# LAN8870_PINOUT.net
KiCad netlist of a schematic drawn in Altium Designer
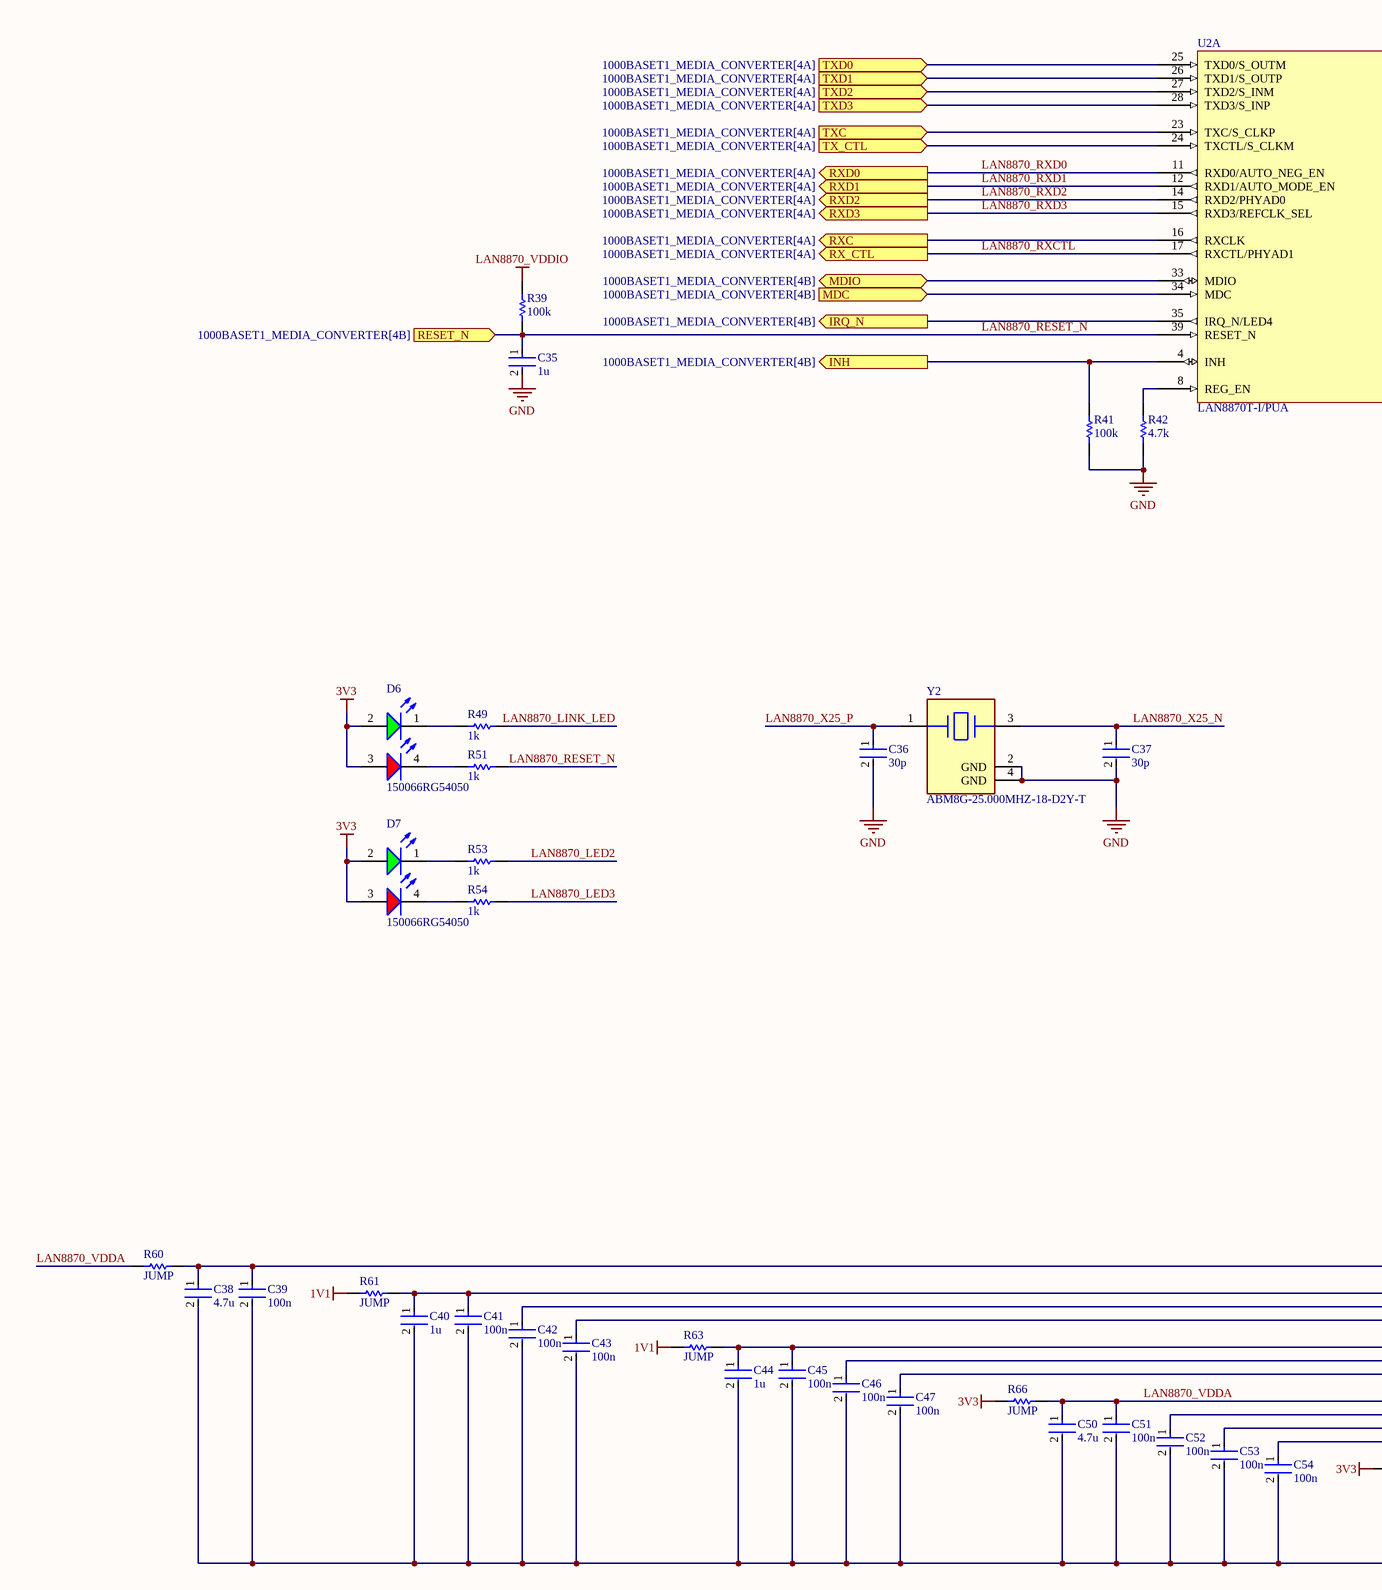
[diagram p0: LAN8870_PINOUT.SchDoc, left]
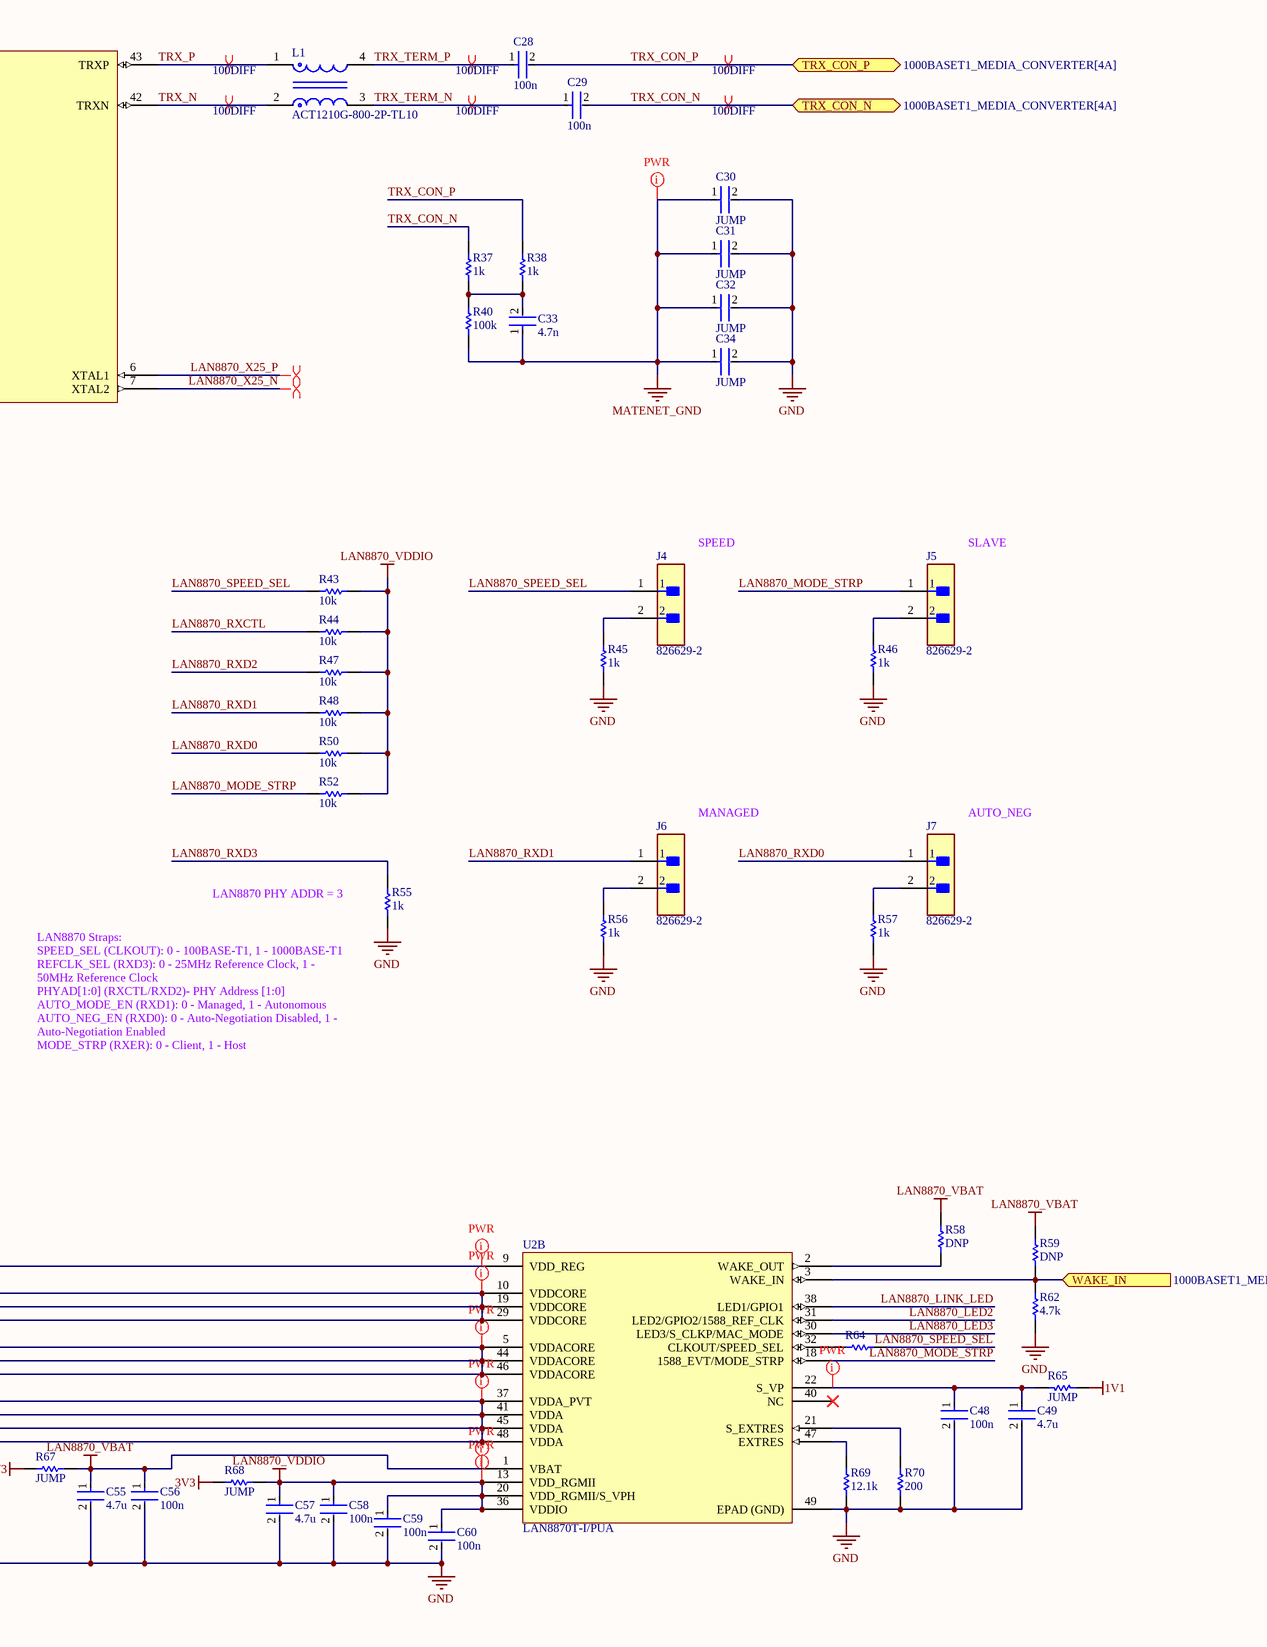
[diagram p1: LAN8870_PINOUT.SchDoc, right]

(export (version "E")
  (design (tool "Eeschema 10.0.6"))
  (components
    (comp (ref "C28")
      (value "100n")
      (footprint "FP-0402-L_1_0_0_05-W_0_5-IPC_A")
      (description "LARGE PADS, 0402 CAP, CHANGE COMMENT TO MATCH REAL P/N")
      (libsource (lib "Space Concordia") (part "b4654b650e69147ec39a6b967a45e02"))
    )
    (comp (ref "C29")
      (value "100n")
      (footprint "FP-0402-L_1_0_0_05-W_0_5-IPC_A")
      (description "LARGE PADS, 0402 CAP, CHANGE COMMENT TO MATCH REAL P/N")
      (libsource (lib "Space Concordia") (part "b4654b650e69147ec39a6b967a45e02"))
    )
    (comp (ref "C30")
      (value "JUMP")
      (footprint "FP-0402-L_1_0_0_05-W_0_5-IPC_A")
      (description "LARGE PADS, 0402 CAP, CHANGE COMMENT TO MATCH REAL P/N")
      (libsource (lib "Space Concordia") (part "b4654b650e69147ec39a6b967a45e02"))
    )
    (comp (ref "C31")
      (value "JUMP")
      (footprint "FP-0402-L_1_0_0_05-W_0_5-IPC_A")
      (description "LARGE PADS, 0402 CAP, CHANGE COMMENT TO MATCH REAL P/N")
      (libsource (lib "Space Concordia") (part "b4654b650e69147ec39a6b967a45e02"))
    )
    (comp (ref "C32")
      (value "JUMP")
      (footprint "FP-0402-L_1_0_0_05-W_0_5-IPC_A")
      (description "LARGE PADS, 0402 CAP, CHANGE COMMENT TO MATCH REAL P/N")
      (libsource (lib "Space Concordia") (part "b4654b650e69147ec39a6b967a45e02"))
    )
    (comp (ref "C33")
      (value "4.7n")
      (footprint "FP-0402-L_1_0_0_05-W_0_5-IPC_A")
      (description "LARGE PADS, 0402 CAP, CHANGE COMMENT TO MATCH REAL P/N")
      (libsource (lib "Space Concordia") (part "b4654b650e69147ec39a6b967a45e02"))
    )
    (comp (ref "C34")
      (value "JUMP")
      (footprint "FP-0402-L_1_0_0_05-W_0_5-IPC_A")
      (description "LARGE PADS, 0402 CAP, CHANGE COMMENT TO MATCH REAL P/N")
      (libsource (lib "Space Concordia") (part "b4654b650e69147ec39a6b967a45e02"))
    )
    (comp (ref "C35")
      (value "1u")
      (footprint "FP-0402-L_1_0_0_05-W_0_5-IPC_A")
      (description "LARGE PADS, 0402 CAP, CHANGE COMMENT TO MATCH REAL P/N")
      (libsource (lib "Space Concordia") (part "b4654b650e69147ec39a6b967a45e02"))
    )
    (comp (ref "C36")
      (value "30p")
      (footprint "FP-0402-L_1_0_0_05-W_0_5-IPC_A")
      (description "LARGE PADS, 0402 CAP, CHANGE COMMENT TO MATCH REAL P/N")
      (libsource (lib "Space Concordia") (part "b4654b650e69147ec39a6b967a45e02"))
    )
    (comp (ref "C37")
      (value "30p")
      (footprint "FP-0402-L_1_0_0_05-W_0_5-IPC_A")
      (description "LARGE PADS, 0402 CAP, CHANGE COMMENT TO MATCH REAL P/N")
      (libsource (lib "Space Concordia") (part "b4654b650e69147ec39a6b967a45e02"))
    )
    (comp (ref "C38")
      (value "4.7u")
      (footprint "FP-0402-L_1_0_0_05-W_0_5-IPC_A")
      (description "LARGE PADS, 0402 CAP, CHANGE COMMENT TO MATCH REAL P/N")
      (libsource (lib "Space Concordia") (part "b4654b650e69147ec39a6b967a45e02"))
    )
    (comp (ref "C39")
      (value "100n")
      (footprint "FP-0402-L_1_0_0_05-W_0_5-IPC_A")
      (description "LARGE PADS, 0402 CAP, CHANGE COMMENT TO MATCH REAL P/N")
      (libsource (lib "Space Concordia") (part "b4654b650e69147ec39a6b967a45e02"))
    )
    (comp (ref "C40")
      (value "1u")
      (footprint "FP-0402-L_1_0_0_05-W_0_5-IPC_A")
      (description "LARGE PADS, 0402 CAP, CHANGE COMMENT TO MATCH REAL P/N")
      (libsource (lib "Space Concordia") (part "b4654b650e69147ec39a6b967a45e02"))
    )
    (comp (ref "C41")
      (value "100n")
      (footprint "FP-0402-L_1_0_0_05-W_0_5-IPC_A")
      (description "LARGE PADS, 0402 CAP, CHANGE COMMENT TO MATCH REAL P/N")
      (libsource (lib "Space Concordia") (part "b4654b650e69147ec39a6b967a45e02"))
    )
    (comp (ref "C42")
      (value "100n")
      (footprint "FP-0402-L_1_0_0_05-W_0_5-IPC_A")
      (description "LARGE PADS, 0402 CAP, CHANGE COMMENT TO MATCH REAL P/N")
      (libsource (lib "Space Concordia") (part "b4654b650e69147ec39a6b967a45e02"))
    )
    (comp (ref "C43")
      (value "100n")
      (footprint "FP-0402-L_1_0_0_05-W_0_5-IPC_A")
      (description "LARGE PADS, 0402 CAP, CHANGE COMMENT TO MATCH REAL P/N")
      (libsource (lib "Space Concordia") (part "b4654b650e69147ec39a6b967a45e02"))
    )
    (comp (ref "C44")
      (value "1u")
      (footprint "FP-0402-L_1_0_0_05-W_0_5-IPC_A")
      (description "LARGE PADS, 0402 CAP, CHANGE COMMENT TO MATCH REAL P/N")
      (libsource (lib "Space Concordia") (part "b4654b650e69147ec39a6b967a45e02"))
    )
    (comp (ref "C45")
      (value "100n")
      (footprint "FP-0402-L_1_0_0_05-W_0_5-IPC_A")
      (description "LARGE PADS, 0402 CAP, CHANGE COMMENT TO MATCH REAL P/N")
      (libsource (lib "Space Concordia") (part "b4654b650e69147ec39a6b967a45e02"))
    )
    (comp (ref "C46")
      (value "100n")
      (footprint "FP-0402-L_1_0_0_05-W_0_5-IPC_A")
      (description "LARGE PADS, 0402 CAP, CHANGE COMMENT TO MATCH REAL P/N")
      (libsource (lib "Space Concordia") (part "b4654b650e69147ec39a6b967a45e02"))
    )
    (comp (ref "C47")
      (value "100n")
      (footprint "FP-0402-L_1_0_0_05-W_0_5-IPC_A")
      (description "LARGE PADS, 0402 CAP, CHANGE COMMENT TO MATCH REAL P/N")
      (libsource (lib "Space Concordia") (part "b4654b650e69147ec39a6b967a45e02"))
    )
    (comp (ref "C48")
      (value "100n")
      (footprint "FP-0402-L_1_0_0_05-W_0_5-IPC_A")
      (description "LARGE PADS, 0402 CAP, CHANGE COMMENT TO MATCH REAL P/N")
      (libsource (lib "Space Concordia") (part "b4654b650e69147ec39a6b967a45e02"))
    )
    (comp (ref "C49")
      (value "4.7u")
      (footprint "FP-0402-L_1_0_0_05-W_0_5-IPC_A")
      (description "LARGE PADS, 0402 CAP, CHANGE COMMENT TO MATCH REAL P/N")
      (libsource (lib "Space Concordia") (part "b4654b650e69147ec39a6b967a45e02"))
    )
    (comp (ref "C50")
      (value "4.7u")
      (footprint "FP-0402-L_1_0_0_05-W_0_5-IPC_A")
      (description "LARGE PADS, 0402 CAP, CHANGE COMMENT TO MATCH REAL P/N")
      (libsource (lib "Space Concordia") (part "b4654b650e69147ec39a6b967a45e02"))
    )
    (comp (ref "C51")
      (value "100n")
      (footprint "FP-0402-L_1_0_0_05-W_0_5-IPC_A")
      (description "LARGE PADS, 0402 CAP, CHANGE COMMENT TO MATCH REAL P/N")
      (libsource (lib "Space Concordia") (part "b4654b650e69147ec39a6b967a45e02"))
    )
    (comp (ref "C52")
      (value "100n")
      (footprint "FP-0402-L_1_0_0_05-W_0_5-IPC_A")
      (description "LARGE PADS, 0402 CAP, CHANGE COMMENT TO MATCH REAL P/N")
      (libsource (lib "Space Concordia") (part "b4654b650e69147ec39a6b967a45e02"))
    )
    (comp (ref "C53")
      (value "100n")
      (footprint "FP-0402-L_1_0_0_05-W_0_5-IPC_A")
      (description "LARGE PADS, 0402 CAP, CHANGE COMMENT TO MATCH REAL P/N")
      (libsource (lib "Space Concordia") (part "b4654b650e69147ec39a6b967a45e02"))
    )
    (comp (ref "C54")
      (value "100n")
      (footprint "FP-0402-L_1_0_0_05-W_0_5-IPC_A")
      (description "LARGE PADS, 0402 CAP, CHANGE COMMENT TO MATCH REAL P/N")
      (libsource (lib "Space Concordia") (part "b4654b650e69147ec39a6b967a45e02"))
    )
    (comp (ref "C55")
      (value "4.7u")
      (footprint "FP-0402-L_1_0_0_05-W_0_5-IPC_A")
      (description "LARGE PADS, 0402 CAP, CHANGE COMMENT TO MATCH REAL P/N")
      (libsource (lib "Space Concordia") (part "b4654b650e69147ec39a6b967a45e02"))
    )
    (comp (ref "C56")
      (value "100n")
      (footprint "FP-0402-L_1_0_0_05-W_0_5-IPC_A")
      (description "LARGE PADS, 0402 CAP, CHANGE COMMENT TO MATCH REAL P/N")
      (libsource (lib "Space Concordia") (part "b4654b650e69147ec39a6b967a45e02"))
    )
    (comp (ref "C57")
      (value "4.7u")
      (footprint "FP-0402-L_1_0_0_05-W_0_5-IPC_A")
      (description "LARGE PADS, 0402 CAP, CHANGE COMMENT TO MATCH REAL P/N")
      (libsource (lib "Space Concordia") (part "b4654b650e69147ec39a6b967a45e02"))
    )
    (comp (ref "C58")
      (value "100n")
      (footprint "FP-0402-L_1_0_0_05-W_0_5-IPC_A")
      (description "LARGE PADS, 0402 CAP, CHANGE COMMENT TO MATCH REAL P/N")
      (libsource (lib "Space Concordia") (part "b4654b650e69147ec39a6b967a45e02"))
    )
    (comp (ref "C59")
      (value "100n")
      (footprint "FP-0402-L_1_0_0_05-W_0_5-IPC_A")
      (description "LARGE PADS, 0402 CAP, CHANGE COMMENT TO MATCH REAL P/N")
      (libsource (lib "Space Concordia") (part "b4654b650e69147ec39a6b967a45e02"))
    )
    (comp (ref "C60")
      (value "100n")
      (footprint "FP-0402-L_1_0_0_05-W_0_5-IPC_A")
      (description "LARGE PADS, 0402 CAP, CHANGE COMMENT TO MATCH REAL P/N")
      (libsource (lib "Space Concordia") (part "b4654b650e69147ec39a6b967a45e02"))
    )
    (comp (ref "D6")
      (value "150066RG54050")
      (footprint "WL-SBCD_0606")
      (description "Led, Red/Grn, 180Mcd/230Mcd, 624Nm/525Nm Rohs Compliant: Yes")
      (fields (field (name "SOURCE") "rgled.SchLib"))
      (libsource (lib "Space Concordia") (part "CMP-004-00034-2"))
    )
    (comp (ref "D7")
      (value "150066RG54050")
      (footprint "WL-SBCD_0606")
      (description "Led, Red/Grn, 180Mcd/230Mcd, 624Nm/525Nm Rohs Compliant: Yes")
      (fields (field (name "SOURCE") "rgled.SchLib"))
      (libsource (lib "Space Concordia") (part "CMP-004-00034-2"))
    )
    (comp (ref "J4")
      (value "826629-2")
      (footprint "FP-826629-2-MFG")
      (description "CONN HEADER VERT 2POS 2.54MM")
      (libsource (lib "Altium Content Vault") (part "3bc925449376181038e59eaffc5286c"))
    )
    (comp (ref "J5")
      (value "826629-2")
      (footprint "FP-826629-2-MFG")
      (description "CONN HEADER VERT 2POS 2.54MM")
      (libsource (lib "Altium Content Vault") (part "3bc925449376181038e59eaffc5286c"))
    )
    (comp (ref "J6")
      (value "826629-2")
      (footprint "FP-826629-2-MFG")
      (description "CONN HEADER VERT 2POS 2.54MM")
      (libsource (lib "Altium Content Vault") (part "3bc925449376181038e59eaffc5286c"))
    )
    (comp (ref "J7")
      (value "826629-2")
      (footprint "FP-826629-2-MFG")
      (description "CONN HEADER VERT 2POS 2.54MM")
      (libsource (lib "Altium Content Vault") (part "3bc925449376181038e59eaffc5286c"))
    )
    (comp (ref "L1")
      (value "ACT1210G-800-2P-TL10")
      (footprint "FP-ACT1210G-800-2P-TL10-MFG")
      (description "CMC 80UH 70MA 2LN 3.8KOHM SMD")
      (libsource (lib "Altium Content Vault") (part "b4b74a627ea9af473eaab86227aab92"))
    )
    (comp (ref "R37")
      (value "1k")
      (footprint "R0603B")
      (description "Resistor")
      (libsource (lib "Space Concordia") (part "Resistor"))
    )
    (comp (ref "R38")
      (value "1k")
      (footprint "R0603B")
      (description "Resistor")
      (libsource (lib "Space Concordia") (part "Resistor"))
    )
    (comp (ref "R39")
      (value "100k")
      (footprint "R0603B")
      (description "Resistor")
      (libsource (lib "Space Concordia") (part "Resistor"))
    )
    (comp (ref "R40")
      (value "100k")
      (footprint "R0603B")
      (description "Resistor")
      (libsource (lib "Space Concordia") (part "Resistor"))
    )
    (comp (ref "R41")
      (value "100k")
      (footprint "R0603B")
      (description "Resistor")
      (libsource (lib "Space Concordia") (part "Resistor"))
    )
    (comp (ref "R42")
      (value "4.7k")
      (footprint "R0603B")
      (description "Resistor")
      (libsource (lib "Space Concordia") (part "Resistor"))
    )
    (comp (ref "R43")
      (value "10k")
      (footprint "R0603B")
      (description "Resistor")
      (libsource (lib "Space Concordia") (part "Resistor"))
    )
    (comp (ref "R44")
      (value "10k")
      (footprint "R0603B")
      (description "Resistor")
      (libsource (lib "Space Concordia") (part "Resistor"))
    )
    (comp (ref "R45")
      (value "1k")
      (footprint "R0603B")
      (description "Resistor")
      (libsource (lib "Space Concordia") (part "Resistor"))
    )
    (comp (ref "R46")
      (value "1k")
      (footprint "R0603B")
      (description "Resistor")
      (libsource (lib "Space Concordia") (part "Resistor"))
    )
    (comp (ref "R47")
      (value "10k")
      (footprint "R0603B")
      (description "Resistor")
      (libsource (lib "Space Concordia") (part "Resistor"))
    )
    (comp (ref "R48")
      (value "10k")
      (footprint "R0603B")
      (description "Resistor")
      (libsource (lib "Space Concordia") (part "Resistor"))
    )
    (comp (ref "R49")
      (value "1k")
      (footprint "R0603B")
      (description "Resistor")
      (libsource (lib "Space Concordia") (part "Resistor"))
    )
    (comp (ref "R50")
      (value "10k")
      (footprint "R0603B")
      (description "Resistor")
      (libsource (lib "Space Concordia") (part "Resistor"))
    )
    (comp (ref "R51")
      (value "1k")
      (footprint "R0603B")
      (description "Resistor")
      (libsource (lib "Space Concordia") (part "Resistor"))
    )
    (comp (ref "R52")
      (value "10k")
      (footprint "R0603B")
      (description "Resistor")
      (libsource (lib "Space Concordia") (part "Resistor"))
    )
    (comp (ref "R53")
      (value "1k")
      (footprint "R0603B")
      (description "Resistor")
      (libsource (lib "Space Concordia") (part "Resistor"))
    )
    (comp (ref "R54")
      (value "1k")
      (footprint "R0603B")
      (description "Resistor")
      (libsource (lib "Space Concordia") (part "Resistor"))
    )
    (comp (ref "R55")
      (value "1k")
      (footprint "R0603B")
      (description "Resistor")
      (libsource (lib "Space Concordia") (part "Resistor"))
    )
    (comp (ref "R56")
      (value "1k")
      (footprint "R0603B")
      (description "Resistor")
      (libsource (lib "Space Concordia") (part "Resistor"))
    )
    (comp (ref "R57")
      (value "1k")
      (footprint "R0603B")
      (description "Resistor")
      (libsource (lib "Space Concordia") (part "Resistor"))
    )
    (comp (ref "R58")
      (value "DNP")
      (footprint "R0603B")
      (description "Resistor")
      (libsource (lib "Space Concordia") (part "Resistor"))
    )
    (comp (ref "R59")
      (value "DNP")
      (footprint "R0603B")
      (description "Resistor")
      (libsource (lib "Space Concordia") (part "Resistor"))
    )
    (comp (ref "R60")
      (value "JUMP")
      (footprint "R0603B")
      (description "Resistor")
      (libsource (lib "Space Concordia") (part "Resistor"))
    )
    (comp (ref "R61")
      (value "JUMP")
      (footprint "R0603B")
      (description "Resistor")
      (libsource (lib "Space Concordia") (part "Resistor"))
    )
    (comp (ref "R62")
      (value "4.7k")
      (footprint "R0603B")
      (description "Resistor")
      (libsource (lib "Space Concordia") (part "Resistor"))
    )
    (comp (ref "R63")
      (value "JUMP")
      (footprint "R0603B")
      (description "Resistor")
      (libsource (lib "Space Concordia") (part "Resistor"))
    )
    (comp (ref "R64")
      (value "0402 JUMPER")
      (footprint "RESC1005X40X25ML05T05")
      (description "READ THE NAME")
      (libsource (lib "Space Concordia") (part "CMP-009-00206-2"))
    )
    (comp (ref "R65")
      (value "JUMP")
      (footprint "R0603B")
      (description "Resistor")
      (libsource (lib "Space Concordia") (part "Resistor"))
    )
    (comp (ref "R66")
      (value "JUMP")
      (footprint "R0603B")
      (description "Resistor")
      (libsource (lib "Space Concordia") (part "Resistor"))
    )
    (comp (ref "R67")
      (value "JUMP")
      (footprint "R0603B")
      (description "Resistor")
      (libsource (lib "Space Concordia") (part "Resistor"))
    )
    (comp (ref "R68")
      (value "JUMP")
      (footprint "R0603B")
      (description "Resistor")
      (libsource (lib "Space Concordia") (part "Resistor"))
    )
    (comp (ref "R69")
      (value "12.1k")
      (footprint "R0603B")
      (description "Resistor")
      (libsource (lib "Space Concordia") (part "Resistor"))
    )
    (comp (ref "R70")
      (value "200")
      (footprint "R0603B")
      (description "Resistor")
      (libsource (lib "Space Concordia") (part "Resistor"))
    )
    (comp (ref "U2")
      (value "LAN8870T-I/PUA")
      (footprint "QFN50P700X700X100_HS-49N")
      (description "100/1000BASE-T1 Rgmii/sgmii Phy")
      (libsource (lib "Space Concordia") (part "LAN8870T-I_PUA"))
    )
    (comp (ref "Y2")
      (value "ABM8G-25.000MHZ-18-D2Y-T")
      (footprint "FP-ABM8G-MFG")
      (description "Crystal 25MHz ±20ppm (Tol) ±30ppm (Stability) 18pF FUND 60Ω 4-Pin SMD T/R")
      (fields (field (name "TOLERANCE") "20ppm"))
      (libsource (lib "Altium Content Vault") (part "48e526d86b7f2615d98721063c72f49"))
    )
  )
  (nets
    (net (code "1") (name "/INH") (class "Default")
      (node (ref "R41") (pin "1") (pinfunction "1_1") (pintype "passive"))
      (node (ref "U2") (pin "4") (pinfunction "INH_4") (pintype "bidirectional"))
    )
    (net (code "2") (name "/IRQ_N") (class "Default")
      (node (ref "U2") (pin "35") (pinfunction "IRQ_N/LED4_35") (pintype "output"))
    )
    (net (code "3") (name "/LAN8870_LED2") (class "Default")
      (node (ref "R53") (pin "2") (pinfunction "2_2") (pintype "passive"))
      (node (ref "U2") (pin "31") (pinfunction "LED2/GPIO2/1588_REF_CLK_31") (pintype "bidirectional"))
    )
    (net (code "4") (name "/LAN8870_LED3") (class "Default")
      (node (ref "R54") (pin "2") (pinfunction "2_2") (pintype "passive"))
      (node (ref "U2") (pin "30") (pinfunction "LED3/S_CLKP/MAC_MODE_30") (pintype "bidirectional"))
    )
    (net (code "5") (name "/LAN8870_LINK_LED") (class "Default")
      (node (ref "R49") (pin "2") (pinfunction "2_2") (pintype "passive"))
      (node (ref "U2") (pin "38") (pinfunction "LED1/GPIO1_38") (pintype "bidirectional"))
    )
    (net (code "6") (name "/LAN8870_MODE_STRP") (class "Default")
      (node (ref "J5") (pin "1") (pinfunction "1_1") (pintype "passive"))
      (node (ref "R52") (pin "1") (pinfunction "1_1") (pintype "passive"))
      (node (ref "U2") (pin "18") (pinfunction "1588_EVT/MODE_STRP_18") (pintype "bidirectional"))
    )
    (net (code "7") (name "/LAN8870_RESET_N") (class "Default")
      (node (ref "C35") (pin "1") (pinfunction "1_1") (pintype "passive"))
      (node (ref "R39") (pin "2") (pinfunction "2_2") (pintype "passive"))
      (node (ref "R51") (pin "2") (pinfunction "2_2") (pintype "passive"))
      (node (ref "U2") (pin "39") (pinfunction "RESET_N_39") (pintype "input"))
    )
    (net (code "8") (name "/LAN8870_RXCTL") (class "Default")
      (node (ref "R44") (pin "2") (pinfunction "2_2") (pintype "passive"))
      (node (ref "U2") (pin "17") (pinfunction "RXCTL/PHYAD1_17") (pintype "output"))
    )
    (net (code "9") (name "/LAN8870_RXD0") (class "Default")
      (node (ref "J7") (pin "1") (pinfunction "1_1") (pintype "passive"))
      (node (ref "R50") (pin "1") (pinfunction "1_1") (pintype "passive"))
      (node (ref "U2") (pin "11") (pinfunction "RXD0/AUTO_NEG_EN_11") (pintype "output"))
    )
    (net (code "10") (name "/LAN8870_RXD1") (class "Default")
      (node (ref "J6") (pin "1") (pinfunction "1_1") (pintype "passive"))
      (node (ref "R48") (pin "1") (pinfunction "1_1") (pintype "passive"))
      (node (ref "U2") (pin "12") (pinfunction "RXD1/AUTO_MODE_EN_12") (pintype "output"))
    )
    (net (code "11") (name "/LAN8870_RXD2") (class "Default")
      (node (ref "R47") (pin "1") (pinfunction "1_1") (pintype "passive"))
      (node (ref "U2") (pin "14") (pinfunction "RXD2/PHYAD0_14") (pintype "output"))
    )
    (net (code "12") (name "/LAN8870_RXD3") (class "Default")
      (node (ref "R55") (pin "2") (pinfunction "2_2") (pintype "passive"))
      (node (ref "U2") (pin "15") (pinfunction "RXD3/REFCLK_SEL_15") (pintype "output"))
    )
    (net (code "13") (name "/LAN8870_SPEED_SEL") (class "Default")
      (node (ref "J4") (pin "1") (pinfunction "1_1") (pintype "passive"))
      (node (ref "R43") (pin "1") (pinfunction "1_1") (pintype "passive"))
      (node (ref "R64") (pin "2") (pinfunction "2_2") (pintype "passive"))
    )
    (net (code "14") (name "/LAN8870_VDDA") (class "Default")
      (node (ref "C50") (pin "1") (pinfunction "1_1") (pintype "passive"))
      (node (ref "C51") (pin "1") (pinfunction "1_1") (pintype "passive"))
      (node (ref "C52") (pin "1") (pinfunction "1_1") (pintype "passive"))
      (node (ref "C53") (pin "1") (pinfunction "1_1") (pintype "passive"))
      (node (ref "C54") (pin "1") (pinfunction "1_1") (pintype "passive"))
      (node (ref "R60") (pin "1") (pinfunction "1_1") (pintype "passive"))
      (node (ref "R66") (pin "2") (pinfunction "2_2") (pintype "passive"))
      (node (ref "U2") (pin "37") (pinfunction "VDDA_PVT_37") (pintype "power_in"))
      (node (ref "U2") (pin "41") (pinfunction "VDDA_41") (pintype "power_in"))
      (node (ref "U2") (pin "45") (pinfunction "VDDA_45") (pintype "power_in"))
      (node (ref "U2") (pin "48") (pinfunction "VDDA_48") (pintype "power_in"))
    )
    (net (code "15") (name "/LAN8870_X25_N") (class "Default")
      (node (ref "C37") (pin "1") (pinfunction "1_1") (pintype "passive"))
      (node (ref "U2") (pin "7") (pinfunction "XTAL2_7") (pintype "output"))
      (node (ref "Y2") (pin "3") (pinfunction "3_3") (pintype "passive"))
    )
    (net (code "16") (name "/LAN8870_X25_P") (class "Default")
      (node (ref "C36") (pin "1") (pinfunction "1_1") (pintype "passive"))
      (node (ref "U2") (pin "6") (pinfunction "XTAL1_6") (pintype "input"))
      (node (ref "Y2") (pin "1") (pinfunction "1_1") (pintype "passive"))
    )
    (net (code "17") (name "/MDC") (class "Default")
      (node (ref "U2") (pin "34") (pinfunction "MDC_34") (pintype "input"))
    )
    (net (code "18") (name "/MDIO") (class "Default")
      (node (ref "U2") (pin "33") (pinfunction "MDIO_33") (pintype "bidirectional"))
    )
    (net (code "19") (name "/RXC") (class "Default")
      (node (ref "U2") (pin "16") (pinfunction "RXCLK_16") (pintype "output"))
    )
    (net (code "20") (name "/TRX_CON_N") (class "Default")
      (node (ref "C29") (pin "2") (pinfunction "2_2") (pintype "passive"))
      (node (ref "R37") (pin "2") (pinfunction "2_2") (pintype "passive"))
    )
    (net (code "21") (name "/TRX_CON_P") (class "Default")
      (node (ref "C28") (pin "2") (pinfunction "2_2") (pintype "passive"))
      (node (ref "R38") (pin "2") (pinfunction "2_2") (pintype "passive"))
    )
    (net (code "22") (name "/TRX_N") (class "Default")
      (node (ref "L1") (pin "2") (pinfunction "2_2") (pintype "passive"))
      (node (ref "U2") (pin "42") (pinfunction "TRXN_42") (pintype "bidirectional"))
    )
    (net (code "23") (name "/TRX_P") (class "Default")
      (node (ref "L1") (pin "1") (pinfunction "1_1") (pintype "passive"))
      (node (ref "U2") (pin "43") (pinfunction "TRXP_43") (pintype "bidirectional"))
    )
    (net (code "24") (name "/TRX_TERM_N") (class "Default")
      (node (ref "C29") (pin "1") (pinfunction "1_1") (pintype "passive"))
      (node (ref "L1") (pin "3") (pinfunction "3_3") (pintype "passive"))
    )
    (net (code "25") (name "/TRX_TERM_P") (class "Default")
      (node (ref "C28") (pin "1") (pinfunction "1_1") (pintype "passive"))
      (node (ref "L1") (pin "4") (pinfunction "4_4") (pintype "passive"))
    )
    (net (code "26") (name "/TXC") (class "Default")
      (node (ref "U2") (pin "23") (pinfunction "TXC/S_CLKP_23") (pintype "input"))
    )
    (net (code "27") (name "/TXD0") (class "Default")
      (node (ref "U2") (pin "25") (pinfunction "TXD0/S_OUTM_25") (pintype "input"))
    )
    (net (code "28") (name "/TXD1") (class "Default")
      (node (ref "U2") (pin "26") (pinfunction "TXD1/S_OUTP_26") (pintype "input"))
    )
    (net (code "29") (name "/TXD2") (class "Default")
      (node (ref "U2") (pin "27") (pinfunction "TXD2/S_INM_27") (pintype "input"))
    )
    (net (code "30") (name "/TXD3") (class "Default")
      (node (ref "U2") (pin "28") (pinfunction "TXD3/S_INP_28") (pintype "input"))
    )
    (net (code "31") (name "/TX_CTL") (class "Default")
      (node (ref "U2") (pin "24") (pinfunction "TXCTL/S_CLKM_24") (pintype "input"))
    )
    (net (code "32") (name "/WAKE_IN") (class "Default")
      (node (ref "R59") (pin "2") (pinfunction "2_2") (pintype "passive"))
      (node (ref "R62") (pin "1") (pinfunction "1_1") (pintype "passive"))
      (node (ref "U2") (pin "3") (pinfunction "WAKE_IN_3") (pintype "bidirectional"))
    )
    (net (code "33") (name "1V1") (class "Default")
      (node (ref "R61") (pin "1") (pinfunction "1_1") (pintype "passive"))
      (node (ref "R63") (pin "1") (pinfunction "1_1") (pintype "passive"))
      (node (ref "R65") (pin "1") (pinfunction "1_1") (pintype "passive"))
    )
    (net (code "34") (name "3V3") (class "Default")
      (node (ref "D6") (pin "2") (pinfunction "A_2") (pintype "passive"))
      (node (ref "D6") (pin "3") (pinfunction "A_3") (pintype "passive"))
      (node (ref "D7") (pin "2") (pinfunction "A_2") (pintype "passive"))
      (node (ref "D7") (pin "3") (pinfunction "A_3") (pintype "passive"))
      (node (ref "R66") (pin "1") (pinfunction "1_1") (pintype "passive"))
      (node (ref "R67") (pin "1") (pinfunction "1_1") (pintype "passive"))
      (node (ref "R68") (pin "1") (pinfunction "1_1") (pintype "passive"))
    )
    (net (code "35") (name "GND") (class "Default")
      (node (ref "C30") (pin "2") (pinfunction "2_2") (pintype "passive"))
      (node (ref "C31") (pin "2") (pinfunction "2_2") (pintype "passive"))
      (node (ref "C32") (pin "2") (pinfunction "2_2") (pintype "passive"))
      (node (ref "C34") (pin "2") (pinfunction "2_2") (pintype "passive"))
      (node (ref "C35") (pin "2") (pinfunction "2_2") (pintype "passive"))
      (node (ref "C36") (pin "2") (pinfunction "2_2") (pintype "passive"))
      (node (ref "C37") (pin "2") (pinfunction "2_2") (pintype "passive"))
      (node (ref "C38") (pin "2") (pinfunction "2_2") (pintype "passive"))
      (node (ref "C39") (pin "2") (pinfunction "2_2") (pintype "passive"))
      (node (ref "C40") (pin "2") (pinfunction "2_2") (pintype "passive"))
      (node (ref "C41") (pin "2") (pinfunction "2_2") (pintype "passive"))
      (node (ref "C42") (pin "2") (pinfunction "2_2") (pintype "passive"))
      (node (ref "C43") (pin "2") (pinfunction "2_2") (pintype "passive"))
      (node (ref "C44") (pin "2") (pinfunction "2_2") (pintype "passive"))
      (node (ref "C45") (pin "2") (pinfunction "2_2") (pintype "passive"))
      (node (ref "C46") (pin "2") (pinfunction "2_2") (pintype "passive"))
      (node (ref "C47") (pin "2") (pinfunction "2_2") (pintype "passive"))
      (node (ref "C48") (pin "2") (pinfunction "2_2") (pintype "passive"))
      (node (ref "C49") (pin "2") (pinfunction "2_2") (pintype "passive"))
      (node (ref "C50") (pin "2") (pinfunction "2_2") (pintype "passive"))
      (node (ref "C51") (pin "2") (pinfunction "2_2") (pintype "passive"))
      (node (ref "C52") (pin "2") (pinfunction "2_2") (pintype "passive"))
      (node (ref "C53") (pin "2") (pinfunction "2_2") (pintype "passive"))
      (node (ref "C54") (pin "2") (pinfunction "2_2") (pintype "passive"))
      (node (ref "C55") (pin "2") (pinfunction "2_2") (pintype "passive"))
      (node (ref "C56") (pin "2") (pinfunction "2_2") (pintype "passive"))
      (node (ref "C57") (pin "2") (pinfunction "2_2") (pintype "passive"))
      (node (ref "C58") (pin "2") (pinfunction "2_2") (pintype "passive"))
      (node (ref "C59") (pin "2") (pinfunction "2_2") (pintype "passive"))
      (node (ref "C60") (pin "2") (pinfunction "2_2") (pintype "passive"))
      (node (ref "R41") (pin "2") (pinfunction "2_2") (pintype "passive"))
      (node (ref "R42") (pin "2") (pinfunction "2_2") (pintype "passive"))
      (node (ref "R45") (pin "1") (pinfunction "1_1") (pintype "passive"))
      (node (ref "R46") (pin "1") (pinfunction "1_1") (pintype "passive"))
      (node (ref "R55") (pin "1") (pinfunction "1_1") (pintype "passive"))
      (node (ref "R56") (pin "1") (pinfunction "1_1") (pintype "passive"))
      (node (ref "R57") (pin "1") (pinfunction "1_1") (pintype "passive"))
      (node (ref "R62") (pin "2") (pinfunction "2_2") (pintype "passive"))
      (node (ref "R69") (pin "2") (pinfunction "2_2") (pintype "passive"))
      (node (ref "R70") (pin "2") (pinfunction "2_2") (pintype "passive"))
      (node (ref "U2") (pin "49") (pinfunction "EPAD_(GND)_49") (pintype "power_in"))
      (node (ref "Y2") (pin "2") (pinfunction "GND_2") (pintype "power_in"))
      (node (ref "Y2") (pin "4") (pinfunction "GND_4") (pintype "power_in"))
    )
    (net (code "36") (name "LAN8870_VBAT") (class "Default")
      (node (ref "C55") (pin "1") (pinfunction "1_1") (pintype "passive"))
      (node (ref "C56") (pin "1") (pinfunction "1_1") (pintype "passive"))
      (node (ref "R58") (pin "1") (pinfunction "1_1") (pintype "passive"))
      (node (ref "R59") (pin "1") (pinfunction "1_1") (pintype "passive"))
      (node (ref "R67") (pin "2") (pinfunction "2_2") (pintype "passive"))
      (node (ref "U2") (pin "1") (pinfunction "VBAT_1") (pintype "power_in"))
    )
    (net (code "37") (name "LAN8870_VDDIO") (class "Default")
      (node (ref "C57") (pin "1") (pinfunction "1_1") (pintype "passive"))
      (node (ref "C58") (pin "1") (pinfunction "1_1") (pintype "passive"))
      (node (ref "C59") (pin "1") (pinfunction "1_1") (pintype "passive"))
      (node (ref "C60") (pin "1") (pinfunction "1_1") (pintype "passive"))
      (node (ref "R39") (pin "1") (pinfunction "1_1") (pintype "passive"))
      (node (ref "R43") (pin "2") (pinfunction "2_2") (pintype "passive"))
      (node (ref "R44") (pin "1") (pinfunction "1_1") (pintype "passive"))
      (node (ref "R47") (pin "2") (pinfunction "2_2") (pintype "passive"))
      (node (ref "R48") (pin "2") (pinfunction "2_2") (pintype "passive"))
      (node (ref "R50") (pin "2") (pinfunction "2_2") (pintype "passive"))
      (node (ref "R52") (pin "2") (pinfunction "2_2") (pintype "passive"))
      (node (ref "R68") (pin "2") (pinfunction "2_2") (pintype "passive"))
      (node (ref "U2") (pin "13") (pinfunction "VDD_RGMII_13") (pintype "power_in"))
      (node (ref "U2") (pin "20") (pinfunction "VDD_RGMII/S_VPH_20") (pintype "power_in"))
      (node (ref "U2") (pin "36") (pinfunction "VDDIO_36") (pintype "power_in"))
    )
    (net (code "38") (name "MATENET_GND") (class "Default")
      (node (ref "C30") (pin "1") (pinfunction "1_1") (pintype "passive"))
      (node (ref "C31") (pin "1") (pinfunction "1_1") (pintype "passive"))
      (node (ref "C32") (pin "1") (pinfunction "1_1") (pintype "passive"))
      (node (ref "C33") (pin "1") (pinfunction "1_1") (pintype "passive"))
      (node (ref "C34") (pin "1") (pinfunction "1_1") (pintype "passive"))
      (node (ref "R40") (pin "2") (pinfunction "2_2") (pintype "passive"))
    )
    (net (code "39") (name "Net-(C33-Pad2)") (class "Default")
      (node (ref "C33") (pin "2") (pinfunction "2_2") (pintype "passive"))
      (node (ref "R37") (pin "1") (pinfunction "1_1") (pintype "passive"))
      (node (ref "R38") (pin "1") (pinfunction "1_1") (pintype "passive"))
      (node (ref "R40") (pin "1") (pinfunction "1_1") (pintype "passive"))
    )
    (net (code "40") (name "Net-(C40-Pad1)") (class "Default")
      (node (ref "C40") (pin "1") (pinfunction "1_1") (pintype "passive"))
      (node (ref "C41") (pin "1") (pinfunction "1_1") (pintype "passive"))
      (node (ref "C42") (pin "1") (pinfunction "1_1") (pintype "passive"))
      (node (ref "C43") (pin "1") (pinfunction "1_1") (pintype "passive"))
      (node (ref "R61") (pin "2") (pinfunction "2_2") (pintype "passive"))
      (node (ref "U2") (pin "10") (pinfunction "VDDCORE_10") (pintype "power_in"))
      (node (ref "U2") (pin "19") (pinfunction "VDDCORE_19") (pintype "power_in"))
      (node (ref "U2") (pin "29") (pinfunction "VDDCORE_29") (pintype "power_in"))
    )
    (net (code "41") (name "Net-(C44-Pad1)") (class "Default")
      (node (ref "C44") (pin "1") (pinfunction "1_1") (pintype "passive"))
      (node (ref "C45") (pin "1") (pinfunction "1_1") (pintype "passive"))
      (node (ref "C46") (pin "1") (pinfunction "1_1") (pintype "passive"))
      (node (ref "C47") (pin "1") (pinfunction "1_1") (pintype "passive"))
      (node (ref "R63") (pin "2") (pinfunction "2_2") (pintype "passive"))
      (node (ref "U2") (pin "44") (pinfunction "VDDACORE_44") (pintype "power_in"))
      (node (ref "U2") (pin "46") (pinfunction "VDDACORE_46") (pintype "power_in"))
      (node (ref "U2") (pin "5") (pinfunction "VDDACORE_5") (pintype "power_in"))
    )
    (net (code "42") (name "Net-(D6-K-Pad1)") (class "Default")
      (node (ref "D6") (pin "1") (pinfunction "K_1") (pintype "passive"))
      (node (ref "R49") (pin "1") (pinfunction "1_1") (pintype "passive"))
    )
    (net (code "43") (name "Net-(D6-K-Pad4)") (class "Default")
      (node (ref "D6") (pin "4") (pinfunction "K_4") (pintype "passive"))
      (node (ref "R51") (pin "1") (pinfunction "1_1") (pintype "passive"))
    )
    (net (code "44") (name "Net-(D7-K-Pad1)") (class "Default")
      (node (ref "D7") (pin "1") (pinfunction "K_1") (pintype "passive"))
      (node (ref "R53") (pin "1") (pinfunction "1_1") (pintype "passive"))
    )
    (net (code "45") (name "Net-(D7-K-Pad4)") (class "Default")
      (node (ref "D7") (pin "4") (pinfunction "K_4") (pintype "passive"))
      (node (ref "R54") (pin "1") (pinfunction "1_1") (pintype "passive"))
    )
    (net (code "46") (name "Net-(J4-Pad2)") (class "Default")
      (node (ref "J4") (pin "2") (pinfunction "2_2") (pintype "passive"))
      (node (ref "R45") (pin "2") (pinfunction "2_2") (pintype "passive"))
    )
    (net (code "47") (name "Net-(J5-Pad2)") (class "Default")
      (node (ref "J5") (pin "2") (pinfunction "2_2") (pintype "passive"))
      (node (ref "R46") (pin "2") (pinfunction "2_2") (pintype "passive"))
    )
    (net (code "48") (name "Net-(J6-Pad2)") (class "Default")
      (node (ref "J6") (pin "2") (pinfunction "2_2") (pintype "passive"))
      (node (ref "R56") (pin "2") (pinfunction "2_2") (pintype "passive"))
    )
    (net (code "49") (name "Net-(J7-Pad2)") (class "Default")
      (node (ref "J7") (pin "2") (pinfunction "2_2") (pintype "passive"))
      (node (ref "R57") (pin "2") (pinfunction "2_2") (pintype "passive"))
    )
    (net (code "50") (name "Net-(U2A-REG_EN)") (class "Default")
      (node (ref "R42") (pin "1") (pinfunction "1_1") (pintype "passive"))
      (node (ref "U2") (pin "8") (pinfunction "REG_EN_8") (pintype "input"))
    )
    (net (code "51") (name "Net-(U2B-CLKOUT{slash}SPEED_SEL)") (class "Default")
      (node (ref "R64") (pin "1") (pinfunction "1_1") (pintype "passive"))
      (node (ref "U2") (pin "32") (pinfunction "CLKOUT/SPEED_SEL_32") (pintype "bidirectional"))
    )
    (net (code "52") (name "Net-(U2B-EXTRES)") (class "Default")
      (node (ref "R69") (pin "1") (pinfunction "1_1") (pintype "passive"))
      (node (ref "U2") (pin "47") (pinfunction "EXTRES_47") (pintype "input"))
    )
    (net (code "53") (name "Net-(U2B-S_EXTRES)") (class "Default")
      (node (ref "R70") (pin "1") (pinfunction "1_1") (pintype "passive"))
      (node (ref "U2") (pin "21") (pinfunction "S_EXTRES_21") (pintype "input"))
    )
    (net (code "54") (name "Net-(U2B-S_VP)") (class "Default")
      (node (ref "C48") (pin "1") (pinfunction "1_1") (pintype "passive"))
      (node (ref "C49") (pin "1") (pinfunction "1_1") (pintype "passive"))
      (node (ref "R65") (pin "2") (pinfunction "2_2") (pintype "passive"))
      (node (ref "U2") (pin "22") (pinfunction "S_VP_22") (pintype "passive"))
    )
    (net (code "55") (name "Net-(U2B-VDD_REG)") (class "Default")
      (node (ref "C38") (pin "1") (pinfunction "1_1") (pintype "passive"))
      (node (ref "C39") (pin "1") (pinfunction "1_1") (pintype "passive"))
      (node (ref "R60") (pin "2") (pinfunction "2_2") (pintype "passive"))
      (node (ref "U2") (pin "9") (pinfunction "VDD_REG_9") (pintype "power_in"))
    )
    (net (code "56") (name "Net-(U2B-WAKE_OUT)") (class "Default")
      (node (ref "R58") (pin "2") (pinfunction "2_2") (pintype "passive"))
      (node (ref "U2") (pin "2") (pinfunction "WAKE_OUT_2") (pintype "output"))
    )
    (net (code "57") (name "unconnected-(U2B-NC-Pad40)") (class "Default")
      (node (ref "U2") (pin "40") (pinfunction "NC_40") (pintype "passive+no_connect"))
    )
  )
)
